# PWM_PPM_FMU3_REV_C.net
KiCad netlist of a schematic drawn in Altium Designer
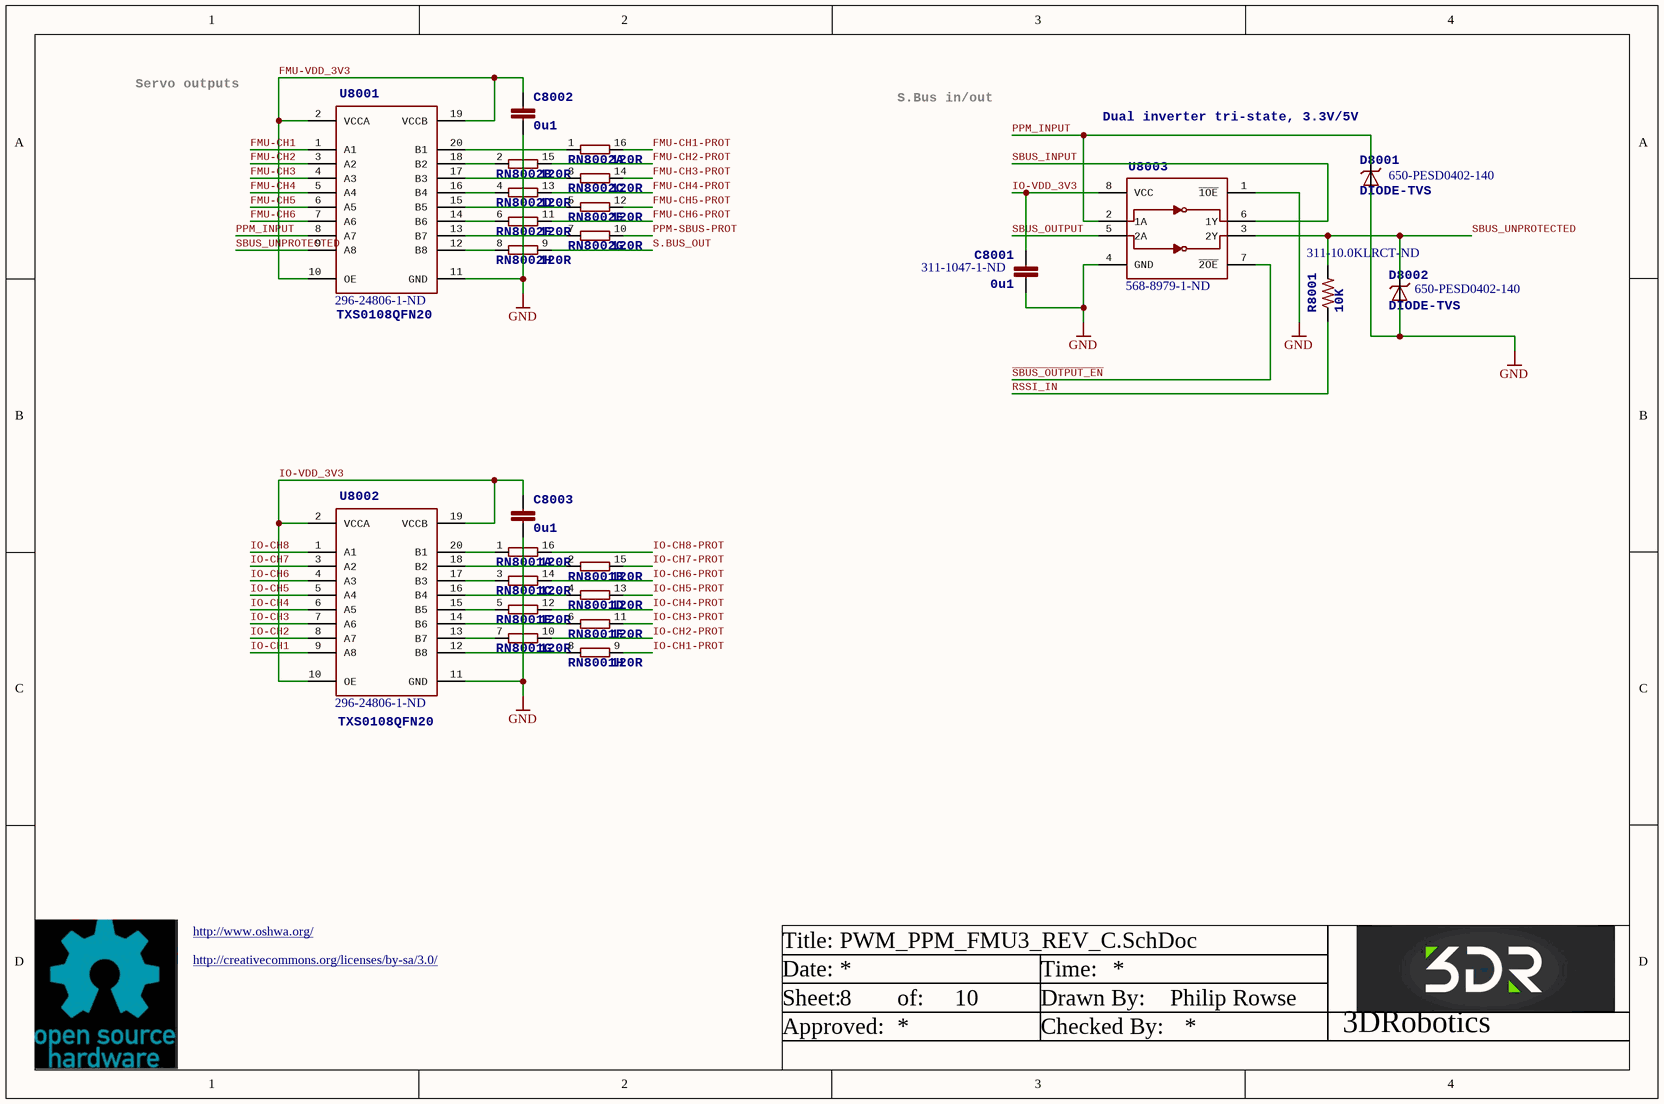
[diagram p0: PWM_PPM_FMU3_REV_C.SchDoc]

(export (version "E")
  (design (tool "Eeschema 10.0.6"))
  (components
    (comp (ref "C8001")
      (value "0u1")
      (footprint "0402-CAP")
      (description "CAP CER 0.1UF 16V Y5V 0402")
      (fields
        (field (name "PARTNO") "CC0402ZRY5V7BB104")
        (field (name "SUPPLIER PART NUMBER 1") "311-1047-1-ND")
        (field (name "3DR_PARTNO") "ECM0700")
      )
      (libsource (lib "pixhawk2") (part "CAP0402"))
    )
    (comp (ref "C8002")
      (value "0u1")
      (footprint "0402-CAP")
      (description "CAP CER 0.1UF 16V Y5V 0402")
      (fields (field (name "PARTNO") "CC0402ZRY5V7BB104") (field (name "3DR_PARTNO") "ECM0700"))
      (libsource (lib "") (part "CAP0402_1"))
    )
    (comp (ref "C8003")
      (value "0u1")
      (footprint "0402-CAP")
      (description "CAP CER 0.1UF 16V Y5V 0402")
      (fields (field (name "PARTNO") "CC0402ZRY5V7BB104") (field (name "3DR_PARTNO") "ECM0700"))
      (libsource (lib "") (part "CAP0402_1"))
    )
    (comp (ref "D8001")
      (value "DIODE-TVS")
      (footprint "0402-TVS")
      (description "TVS DIODE 14VWM 40VC 0402")
      (fields
        (field (name "SUPPLIER PART NUMBER 1") "650-PESD0402-140")
        (field (name "3DR_PARTNO") "ECM0837")
        (field (name "PARTNO") "PESD0402-140")
      )
      (libsource (lib "pixhawk2") (part "DIODE-TVS"))
    )
    (comp (ref "D8002")
      (value "DIODE-TVS")
      (footprint "0402-TVS")
      (description "TVS DIODE 14VWM 40VC 0402")
      (fields
        (field (name "SUPPLIER PART NUMBER 1") "650-PESD0402-140")
        (field (name "3DR_PARTNO") "ECM0837")
        (field (name "PARTNO") "PESD0402-140")
      )
      (libsource (lib "pixhawk2") (part "DIODE-TVS"))
    )
    (comp (ref "R8001")
      (value "10K")
      (footprint "0402-RES")
      (description "RES 10K OHM 1/16W 1% 0402 SMD")
      (fields
        (field (name "PARTNO") "RC0402FR-0710KL")
        (field (name "SUPPLIER PART NUMBER 1") "311-10.0KLRCT-ND")
        (field (name "3DR_PARTNO") "ECM0800")
      )
      (libsource (lib "pixhawk2") (part "RESISTOR0402-RES"))
    )
    (comp (ref "RN8001")
      (value "120R")
      (footprint "EXB2HV")
      (description "RES ARRAY 120 OHM 8 RES 1506")
      (fields (field (name "PARTNO") "EXB-2HV121JV") (field (name "3DR_PARTNO") "ECM0266"))
      (libsource (lib "pixhawk2") (part "8R-NEXB2HV-220R"))
    )
    (comp (ref "RN8002")
      (value "120R")
      (footprint "EXB2HV")
      (description "RES ARRAY 120 OHM 8 RES 1506")
      (fields (field (name "PARTNO") "EXB-2HV121JV") (field (name "3DR_PARTNO") "ECM0266"))
      (libsource (lib "pixhawk2") (part "8R-NEXB2HV-220R"))
    )
    (comp (ref "U8001")
      (value "TXS0108QFN20")
      (footprint "QFN20-RGY")
      (description "IC XLATR VOLT-LVL 8B BDIR 20QFN")
      (fields
        (field (name "SUPPLIER PART NUMBER 1") "296-24806-1-ND")
        (field (name "3DR_PARTNO") "ECM0845")
        (field (name "PARTNO") "TXS0108ERGYR")
      )
      (libsource (lib "pixhawk2") (part "TXS0108QFN20"))
    )
    (comp (ref "U8002")
      (value "TXS0108QFN20")
      (footprint "QFN20-RGY")
      (description "IC XLATR VOLT-LVL 8B BDIR 20QFN")
      (fields
        (field (name "SUPPLIER PART NUMBER 1") "296-24806-1-ND")
        (field (name "3DR_PARTNO") "ECM0845")
        (field (name "PARTNO") "TXS0108ERGYR")
      )
      (libsource (lib "pixhawk2") (part "TXS0108QFN20"))
    )
    (comp (ref "U8003")
      (value "Dual inverter tri-state, 3.3V/5V")
      (footprint "TSSOP8_SOT505-2")
      (description "IC INVERTER DUAL 4-INPUT 8TSSOP")
      (fields
        (field (name "SUPPLIER PART NUMBER 1") "568-8979-1-ND")
        (field (name "3DR_PARTNO") "ECM0817")
        (field (name "PARTNO") "74LVC2G240DP,125")
      )
      (libsource (lib "pixhawk2") (part "74LVC2G240-TSSOP-8"))
    )
  )
  (nets
    (net (code "1") (name "/FMU-CH1") (class "Default")
      (node (ref "U8001") (pin "1") (pinfunction "A1_1") (pintype "passive"))
    )
    (net (code "2") (name "/FMU-CH1-PROT") (class "Default")
      (node (ref "RN8002") (pin "16") (pinfunction "2_16") (pintype "passive"))
    )
    (net (code "3") (name "/FMU-CH2") (class "Default")
      (node (ref "U8001") (pin "3") (pinfunction "A2_3") (pintype "passive"))
    )
    (net (code "4") (name "/FMU-CH2-PROT") (class "Default")
      (node (ref "RN8002") (pin "15") (pinfunction "2_15") (pintype "passive"))
    )
    (net (code "5") (name "/FMU-CH3") (class "Default")
      (node (ref "U8001") (pin "4") (pinfunction "A3_4") (pintype "passive"))
    )
    (net (code "6") (name "/FMU-CH3-PROT") (class "Default")
      (node (ref "RN8002") (pin "14") (pinfunction "2_14") (pintype "passive"))
    )
    (net (code "7") (name "/FMU-CH4") (class "Default")
      (node (ref "U8001") (pin "5") (pinfunction "A4_5") (pintype "passive"))
    )
    (net (code "8") (name "/FMU-CH4-PROT") (class "Default")
      (node (ref "RN8002") (pin "13") (pinfunction "2_13") (pintype "passive"))
    )
    (net (code "9") (name "/FMU-CH5") (class "Default")
      (node (ref "U8001") (pin "6") (pinfunction "A5_6") (pintype "passive"))
    )
    (net (code "10") (name "/FMU-CH5-PROT") (class "Default")
      (node (ref "RN8002") (pin "12") (pinfunction "2_12") (pintype "passive"))
    )
    (net (code "11") (name "/FMU-CH6") (class "Default")
      (node (ref "U8001") (pin "7") (pinfunction "A6_7") (pintype "passive"))
    )
    (net (code "12") (name "/FMU-CH6-PROT") (class "Default")
      (node (ref "RN8002") (pin "11") (pinfunction "2_11") (pintype "passive"))
    )
    (net (code "13") (name "/FMU-VDD_3V3") (class "Default")
      (node (ref "C8002") (pin "P$1") (pinfunction "1_P$1") (pintype "passive"))
      (node (ref "U8001") (pin "10") (pinfunction "OE_10") (pintype "passive"))
      (node (ref "U8001") (pin "19") (pinfunction "VCCB_19") (pintype "passive"))
      (node (ref "U8001") (pin "2") (pinfunction "VCCA_2") (pintype "passive"))
    )
    (net (code "14") (name "/IO-CH1") (class "Default")
      (node (ref "U8002") (pin "9") (pinfunction "A8_9") (pintype "passive"))
    )
    (net (code "15") (name "/IO-CH1-PROT") (class "Default")
      (node (ref "RN8001") (pin "9") (pinfunction "2_9") (pintype "passive"))
    )
    (net (code "16") (name "/IO-CH2") (class "Default")
      (node (ref "U8002") (pin "8") (pinfunction "A7_8") (pintype "passive"))
    )
    (net (code "17") (name "/IO-CH2-PROT") (class "Default")
      (node (ref "RN8001") (pin "10") (pinfunction "2_10") (pintype "passive"))
    )
    (net (code "18") (name "/IO-CH3") (class "Default")
      (node (ref "U8002") (pin "7") (pinfunction "A6_7") (pintype "passive"))
    )
    (net (code "19") (name "/IO-CH3-PROT") (class "Default")
      (node (ref "RN8001") (pin "11") (pinfunction "2_11") (pintype "passive"))
    )
    (net (code "20") (name "/IO-CH4") (class "Default")
      (node (ref "U8002") (pin "6") (pinfunction "A5_6") (pintype "passive"))
    )
    (net (code "21") (name "/IO-CH4-PROT") (class "Default")
      (node (ref "RN8001") (pin "12") (pinfunction "2_12") (pintype "passive"))
    )
    (net (code "22") (name "/IO-CH5") (class "Default")
      (node (ref "U8002") (pin "5") (pinfunction "A4_5") (pintype "passive"))
    )
    (net (code "23") (name "/IO-CH5-PROT") (class "Default")
      (node (ref "RN8001") (pin "13") (pinfunction "2_13") (pintype "passive"))
    )
    (net (code "24") (name "/IO-CH6") (class "Default")
      (node (ref "U8002") (pin "4") (pinfunction "A3_4") (pintype "passive"))
    )
    (net (code "25") (name "/IO-CH6-PROT") (class "Default")
      (node (ref "RN8001") (pin "14") (pinfunction "2_14") (pintype "passive"))
    )
    (net (code "26") (name "/IO-CH7") (class "Default")
      (node (ref "U8002") (pin "3") (pinfunction "A2_3") (pintype "passive"))
    )
    (net (code "27") (name "/IO-CH7-PROT") (class "Default")
      (node (ref "RN8001") (pin "15") (pinfunction "2_15") (pintype "passive"))
    )
    (net (code "28") (name "/IO-CH8") (class "Default")
      (node (ref "U8002") (pin "1") (pinfunction "A1_1") (pintype "passive"))
    )
    (net (code "29") (name "/IO-CH8-PROT") (class "Default")
      (node (ref "RN8001") (pin "16") (pinfunction "2_16") (pintype "passive"))
    )
    (net (code "30") (name "/IO-VDD_3V3") (class "Default")
      (node (ref "C8001") (pin "P$1") (pinfunction "1_P$1") (pintype "passive"))
      (node (ref "C8003") (pin "P$1") (pinfunction "1_P$1") (pintype "passive"))
      (node (ref "U8002") (pin "10") (pinfunction "OE_10") (pintype "passive"))
      (node (ref "U8002") (pin "19") (pinfunction "VCCB_19") (pintype "passive"))
      (node (ref "U8002") (pin "2") (pinfunction "VCCA_2") (pintype "passive"))
      (node (ref "U8003") (pin "8") (pinfunction "VCC_8") (pintype "open_emitter"))
    )
    (net (code "31") (name "/PPM-SBUS-PROT") (class "Default")
      (node (ref "RN8002") (pin "10") (pinfunction "2_10") (pintype "passive"))
    )
    (net (code "32") (name "/PPM_INPUT") (class "Default")
      (node (ref "D8001") (pin "C") (pinfunction "C_C") (pintype "passive"))
      (node (ref "U8001") (pin "8") (pinfunction "A7_8") (pintype "passive"))
      (node (ref "U8003") (pin "2") (pinfunction "1A_2") (pintype "passive"))
    )
    (net (code "33") (name "/RSSI_IN") (class "Default")
      (node (ref "R8001") (pin "P$1") (pinfunction "1_P$1") (pintype "passive"))
    )
    (net (code "34") (name "/S.BUS_OUT") (class "Default")
      (node (ref "RN8002") (pin "9") (pinfunction "2_9") (pintype "passive"))
    )
    (net (code "35") (name "/SBUS_INPUT") (class "Default")
      (node (ref "U8003") (pin "6") (pinfunction "1Y_6") (pintype "passive"))
    )
    (net (code "36") (name "/SBUS_OUTPUT") (class "Default")
      (node (ref "U8003") (pin "5") (pinfunction "2A_5") (pintype "passive"))
    )
    (net (code "37") (name "/SBUS_UNPROTECTED") (class "Default")
      (node (ref "D8002") (pin "C") (pinfunction "C_C") (pintype "passive"))
      (node (ref "R8001") (pin "P$2") (pinfunction "2_P$2") (pintype "passive"))
      (node (ref "U8001") (pin "9") (pinfunction "A8_9") (pintype "passive"))
      (node (ref "U8003") (pin "3") (pinfunction "2Y_3") (pintype "passive"))
    )
    (net (code "38") (name "/~{SBUS_OUTPUT_EN}") (class "Default")
      (node (ref "U8003") (pin "7") (pinfunction "~{2OE}_7") (pintype "passive"))
    )
    (net (code "39") (name "GND") (class "Default")
      (node (ref "C8001") (pin "P$2") (pinfunction "2_P$2") (pintype "passive"))
      (node (ref "C8002") (pin "P$2") (pinfunction "2_P$2") (pintype "passive"))
      (node (ref "C8003") (pin "P$2") (pinfunction "2_P$2") (pintype "passive"))
      (node (ref "D8001") (pin "A") (pinfunction "A_A") (pintype "passive"))
      (node (ref "D8002") (pin "A") (pinfunction "A_A") (pintype "passive"))
      (node (ref "U8001") (pin "11") (pinfunction "GND_11") (pintype "open_emitter"))
      (node (ref "U8002") (pin "11") (pinfunction "GND_11") (pintype "open_emitter"))
      (node (ref "U8003") (pin "1") (pinfunction "~{1OE}_1") (pintype "passive"))
      (node (ref "U8003") (pin "4") (pinfunction "GND_4") (pintype "open_emitter"))
    )
    (net (code "40") (name "Net-(RN8001B-1)") (class "Default")
      (node (ref "RN8001") (pin "2") (pinfunction "1_2") (pintype "passive"))
      (node (ref "U8002") (pin "18") (pinfunction "B2_18") (pintype "passive"))
    )
    (net (code "41") (name "Net-(RN8001C-1)") (class "Default")
      (node (ref "RN8001") (pin "3") (pinfunction "1_3") (pintype "passive"))
      (node (ref "U8002") (pin "17") (pinfunction "B3_17") (pintype "passive"))
    )
    (net (code "42") (name "Net-(RN8001D-1)") (class "Default")
      (node (ref "RN8001") (pin "4") (pinfunction "1_4") (pintype "passive"))
      (node (ref "U8002") (pin "16") (pinfunction "B4_16") (pintype "passive"))
    )
    (net (code "43") (name "Net-(RN8001E-1)") (class "Default")
      (node (ref "RN8001") (pin "5") (pinfunction "1_5") (pintype "passive"))
      (node (ref "U8002") (pin "15") (pinfunction "B5_15") (pintype "passive"))
    )
    (net (code "44") (name "Net-(RN8001F-1)") (class "Default")
      (node (ref "RN8001") (pin "6") (pinfunction "1_6") (pintype "passive"))
      (node (ref "U8002") (pin "14") (pinfunction "B6_14") (pintype "passive"))
    )
    (net (code "45") (name "Net-(RN8001G-1)") (class "Default")
      (node (ref "RN8001") (pin "7") (pinfunction "1_7") (pintype "passive"))
      (node (ref "U8002") (pin "13") (pinfunction "B7_13") (pintype "passive"))
    )
    (net (code "46") (name "Net-(RN8001H-1)") (class "Default")
      (node (ref "RN8001") (pin "8") (pinfunction "1_8") (pintype "passive"))
      (node (ref "U8002") (pin "12") (pinfunction "B8_12") (pintype "passive"))
    )
    (net (code "47") (name "Net-(RN8002B-1)") (class "Default")
      (node (ref "RN8002") (pin "2") (pinfunction "1_2") (pintype "passive"))
      (node (ref "U8001") (pin "18") (pinfunction "B2_18") (pintype "passive"))
    )
    (net (code "48") (name "Net-(RN8002C-1)") (class "Default")
      (node (ref "RN8002") (pin "3") (pinfunction "1_3") (pintype "passive"))
      (node (ref "U8001") (pin "17") (pinfunction "B3_17") (pintype "passive"))
    )
    (net (code "49") (name "Net-(RN8002D-1)") (class "Default")
      (node (ref "RN8002") (pin "4") (pinfunction "1_4") (pintype "passive"))
      (node (ref "U8001") (pin "16") (pinfunction "B4_16") (pintype "passive"))
    )
    (net (code "50") (name "Net-(RN8002E-1)") (class "Default")
      (node (ref "RN8002") (pin "5") (pinfunction "1_5") (pintype "passive"))
      (node (ref "U8001") (pin "15") (pinfunction "B5_15") (pintype "passive"))
    )
    (net (code "51") (name "Net-(RN8002F-1)") (class "Default")
      (node (ref "RN8002") (pin "6") (pinfunction "1_6") (pintype "passive"))
      (node (ref "U8001") (pin "14") (pinfunction "B6_14") (pintype "passive"))
    )
    (net (code "52") (name "Net-(RN8002G-1)") (class "Default")
      (node (ref "RN8002") (pin "7") (pinfunction "1_7") (pintype "passive"))
      (node (ref "U8001") (pin "13") (pinfunction "B7_13") (pintype "passive"))
    )
    (net (code "53") (name "Net-(RN8002H-1)") (class "Default")
      (node (ref "RN8002") (pin "8") (pinfunction "1_8") (pintype "passive"))
      (node (ref "U8001") (pin "12") (pinfunction "B8_12") (pintype "passive"))
    )
    (net (code "54") (name "Net-(U8001-B1)") (class "Default")
      (node (ref "RN8002") (pin "1") (pinfunction "1_1") (pintype "passive"))
      (node (ref "U8001") (pin "20") (pinfunction "B1_20") (pintype "passive"))
    )
    (net (code "55") (name "Net-(U8002-B1)") (class "Default")
      (node (ref "RN8001") (pin "1") (pinfunction "1_1") (pintype "passive"))
      (node (ref "U8002") (pin "20") (pinfunction "B1_20") (pintype "passive"))
    )
  )
)
